# lab2_kondratchenko_buck_boost.net
KiCad netlist of a schematic drawn in Altium Designer
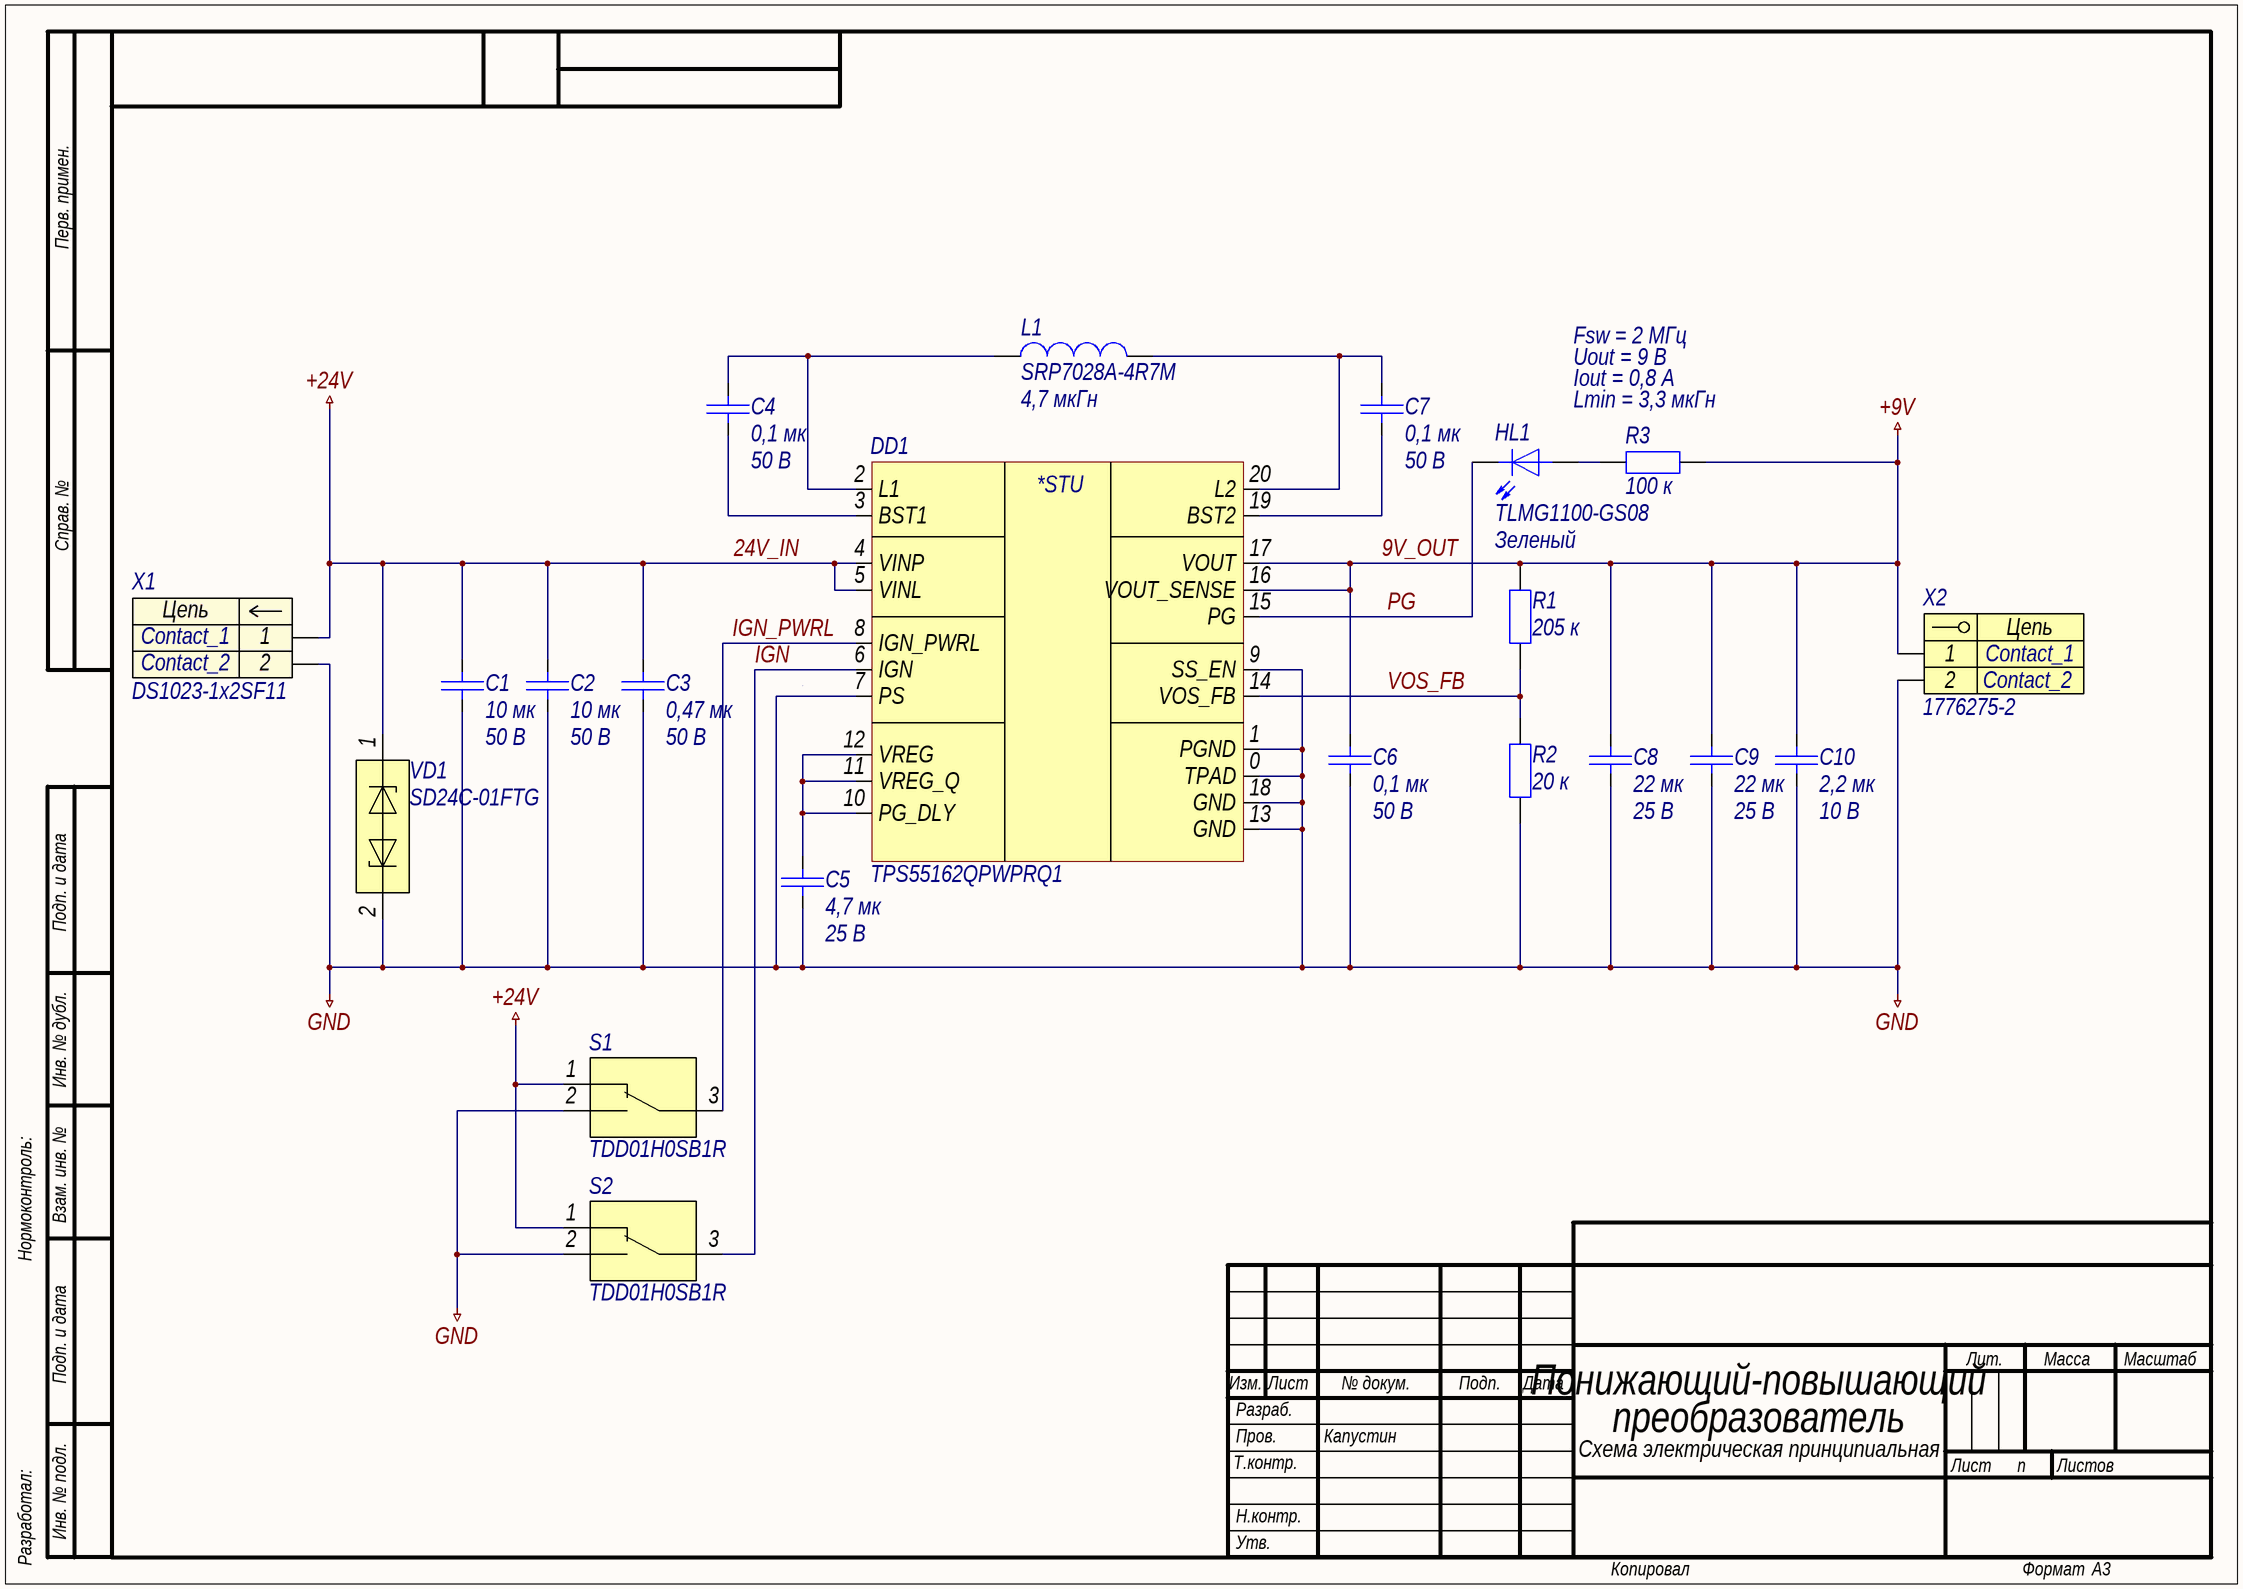
[diagram p0: lab2_kondratchenko_buck_boost.SchDoc]

(export (version "E")
  (design (tool "Eeschema 10.0.6"))
  (components
    (comp (ref "C1")
      (value "10 мк")
      (footprint "C1210")
      (description "=Описание")
      (fields (field (name "НАПРЯЖЕНИЕ") "50 В"))
      (libsource (lib "Database_Students") (part "CAPACITOR-NONPOLAR"))
    )
    (comp (ref "C2")
      (value "10 мк")
      (footprint "C1210")
      (description "=Описание")
      (fields (field (name "НАПРЯЖЕНИЕ") "50 В"))
      (libsource (lib "Database_Students") (part "CAPACITOR-NONPOLAR"))
    )
    (comp (ref "C3")
      (value "0,47 мк")
      (footprint "C0603")
      (description "=Описание")
      (fields (field (name "НАПРЯЖЕНИЕ") "50 В"))
      (libsource (lib "Database_Students") (part "CAPACITOR-NONPOLAR"))
    )
    (comp (ref "C4")
      (value "0,1 мк")
      (footprint "C0603")
      (description "=Описание")
      (fields (field (name "НАПРЯЖЕНИЕ") "50 В"))
      (libsource (lib "Database_Students") (part "CAPACITOR-NONPOLAR"))
    )
    (comp (ref "C5")
      (value "4,7 мк")
      (footprint "C0603")
      (description "=Описание")
      (fields (field (name "НАПРЯЖЕНИЕ") "25 В"))
      (libsource (lib "Database_Students") (part "CAPACITOR-NONPOLAR"))
    )
    (comp (ref "C6")
      (value "0,1 мк")
      (footprint "C0603")
      (description "=Описание")
      (fields (field (name "НАПРЯЖЕНИЕ") "50 В"))
      (libsource (lib "Database_Students") (part "CAPACITOR-NONPOLAR"))
    )
    (comp (ref "C7")
      (value "0,1 мк")
      (footprint "C0603")
      (description "=Описание")
      (fields (field (name "НАПРЯЖЕНИЕ") "50 В"))
      (libsource (lib "Database_Students") (part "CAPACITOR-NONPOLAR"))
    )
    (comp (ref "C8")
      (value "22 мк")
      (footprint "C1210")
      (description "=Описание")
      (fields (field (name "НАПРЯЖЕНИЕ") "25 В"))
      (libsource (lib "Database_Students") (part "CAPACITOR-NONPOLAR"))
    )
    (comp (ref "C9")
      (value "22 мк")
      (footprint "C1210")
      (description "=Описание")
      (fields (field (name "НАПРЯЖЕНИЕ") "25 В"))
      (libsource (lib "Database_Students") (part "CAPACITOR-NONPOLAR"))
    )
    (comp (ref "C10")
      (value "2,2 мк")
      (footprint "C0603")
      (description "=Описание")
      (fields (field (name "НАПРЯЖЕНИЕ") "10 В"))
      (libsource (lib "Database_Students") (part "CAPACITOR-NONPOLAR"))
    )
    (comp (ref "DD1")
      (value "TPS55162QPWPRQ1")
      (footprint "HTSSOP-20-P65-650X440X120-L63X25-T343X275")
      (description "=Описание")
      (libsource (lib "Database_Students") (part "TPS55162QPWPRQ1"))
    )
    (comp (ref "HL1")
      (value "TLMG1100-GS08")
      (footprint "HL0603")
      (description "=Описание")
      (fields (field (name "ЦВЕТ") "Зеленый"))
      (libsource (lib "Database_Students") (part "LED-COMMON"))
    )
    (comp (ref "L1")
      (value "SRP7028A-4R7M")
      (footprint "SRP-2-730X660X280")
      (description "=Описание")
      (fields (field (name "ИНДУКТИВНОСТЬ") "4,7 мкГн"))
      (libsource (lib "Database_Students") (part "INDUCTOR-COMMON"))
    )
    (comp (ref "R1")
      (value "205 к")
      (footprint "R0603")
      (description "=Описание")
      (libsource (lib "Database_Students") (part "RESISTOR-COMMON"))
    )
    (comp (ref "R2")
      (value "20 к")
      (footprint "R0603")
      (description "=Описание")
      (libsource (lib "Database_Students") (part "RESISTOR-COMMON"))
    )
    (comp (ref "R3")
      (value "100 к")
      (footprint "R0603")
      (description "=Описание")
      (libsource (lib "Database_Students") (part "RESISTOR-COMMON"))
    )
    (comp (ref "S1")
      (value "TDD01H0SB1R")
      (footprint "TDD01H0SB1R")
      (description "=Описание")
      (libsource (lib "Database_Students") (part "SWITCH-3C"))
    )
    (comp (ref "S2")
      (value "TDD01H0SB1R")
      (footprint "TDD01H0SB1R")
      (description "=Описание")
      (libsource (lib "Database_Students") (part "SWITCH-3C"))
    )
    (comp (ref "VD1")
      (value "SD24C-01FTG")
      (footprint "SOD-323-257X130X114")
      (description "=Описание")
      (libsource (lib "Database_Students") (part "ZENER-BI-DIRECTIONAL"))
    )
    (comp (ref "X1")
      (value "DS1023-1x2SF11")
      (footprint "DS1069-2MRW6XB")
      (description "=Описание")
      (libsource (lib "Database_Students") (part "HEADER-2-PLG"))
    )
    (comp (ref "X2")
      (value "1776275-2")
      (footprint "1776275-2")
      (description "=Описание")
      (libsource (lib "Database_Students") (part "HEADER-2-TRM"))
    )
  )
  (nets
    (net (code "1") (name "+9V") (class "Default")
      (node (ref "C10") (pin "2") (pinfunction "2_2") (pintype "passive"))
      (node (ref "C6") (pin "2") (pinfunction "2_2") (pintype "passive"))
      (node (ref "C8") (pin "2") (pinfunction "2_2") (pintype "passive"))
      (node (ref "C9") (pin "2") (pinfunction "2_2") (pintype "passive"))
      (node (ref "DD1") (pin "16") (pinfunction "VOUT_SENSE_16") (pintype "passive"))
      (node (ref "DD1") (pin "17") (pinfunction "VOUT_17") (pintype "passive"))
      (node (ref "R1") (pin "1") (pinfunction "1_1") (pintype "passive"))
      (node (ref "R3") (pin "2") (pinfunction "2_2") (pintype "passive"))
      (node (ref "X2") (pin "1") (pinfunction "1_1") (pintype "passive"))
    )
    (net (code "2") (name "+24V") (class "Default")
      (node (ref "C1") (pin "2") (pinfunction "2_2") (pintype "passive"))
      (node (ref "C2") (pin "2") (pinfunction "2_2") (pintype "passive"))
      (node (ref "C3") (pin "2") (pinfunction "2_2") (pintype "passive"))
      (node (ref "DD1") (pin "4") (pinfunction "VINP_4") (pintype "passive"))
      (node (ref "DD1") (pin "5") (pinfunction "VINL_5") (pintype "passive"))
      (node (ref "S1") (pin "1") (pinfunction "1_1") (pintype "passive"))
      (node (ref "S2") (pin "1") (pinfunction "1_1") (pintype "passive"))
      (node (ref "VD1") (pin "1") (pinfunction "1_1") (pintype "passive"))
      (node (ref "X1") (pin "1") (pinfunction "1_1") (pintype "passive"))
    )
    (net (code "3") (name "/IGN") (class "Default")
      (node (ref "DD1") (pin "6") (pinfunction "IGN_6") (pintype "passive"))
      (node (ref "S2") (pin "3") (pinfunction "3_3") (pintype "passive"))
    )
    (net (code "4") (name "/IGN_PWRL") (class "Default")
      (node (ref "DD1") (pin "8") (pinfunction "IGN_PWRL_8") (pintype "passive"))
      (node (ref "S1") (pin "3") (pinfunction "3_3") (pintype "passive"))
    )
    (net (code "5") (name "/PG") (class "Default")
      (node (ref "DD1") (pin "15") (pinfunction "PG_15") (pintype "passive"))
      (node (ref "HL1") (pin "1") (pinfunction "1_1") (pintype "passive"))
    )
    (net (code "6") (name "/VOS_FB") (class "Default")
      (node (ref "DD1") (pin "14") (pinfunction "VOS_FB_14") (pintype "passive"))
      (node (ref "R1") (pin "2") (pinfunction "2_2") (pintype "passive"))
      (node (ref "R2") (pin "2") (pinfunction "2_2") (pintype "passive"))
    )
    (net (code "7") (name "GND") (class "Default")
      (node (ref "C1") (pin "1") (pinfunction "1_1") (pintype "passive"))
      (node (ref "C10") (pin "1") (pinfunction "1_1") (pintype "passive"))
      (node (ref "C2") (pin "1") (pinfunction "1_1") (pintype "passive"))
      (node (ref "C3") (pin "1") (pinfunction "1_1") (pintype "passive"))
      (node (ref "C5") (pin "2") (pinfunction "2_2") (pintype "passive"))
      (node (ref "C6") (pin "1") (pinfunction "1_1") (pintype "passive"))
      (node (ref "C8") (pin "1") (pinfunction "1_1") (pintype "passive"))
      (node (ref "C9") (pin "1") (pinfunction "1_1") (pintype "passive"))
      (node (ref "DD1") (pin "0") (pinfunction "TPAD_0") (pintype "passive"))
      (node (ref "DD1") (pin "1") (pinfunction "PGND_1") (pintype "passive"))
      (node (ref "DD1") (pin "13") (pinfunction "GND_13") (pintype "passive"))
      (node (ref "DD1") (pin "18") (pinfunction "GND_18") (pintype "passive"))
      (node (ref "DD1") (pin "7") (pinfunction "PS_7") (pintype "passive"))
      (node (ref "DD1") (pin "9") (pinfunction "SS_EN_9") (pintype "passive"))
      (node (ref "R2") (pin "1") (pinfunction "1_1") (pintype "passive"))
      (node (ref "S1") (pin "2") (pinfunction "2_2") (pintype "passive"))
      (node (ref "S2") (pin "2") (pinfunction "2_2") (pintype "passive"))
      (node (ref "VD1") (pin "2") (pinfunction "2_2") (pintype "passive"))
      (node (ref "X1") (pin "2") (pinfunction "2_2") (pintype "passive"))
      (node (ref "X2") (pin "2") (pinfunction "2_2") (pintype "passive"))
    )
    (net (code "8") (name "Net-(DD1-BST1)") (class "Default")
      (node (ref "C4") (pin "1") (pinfunction "1_1") (pintype "passive"))
      (node (ref "DD1") (pin "3") (pinfunction "BST1_3") (pintype "passive"))
    )
    (net (code "9") (name "Net-(DD1-BST2)") (class "Default")
      (node (ref "C7") (pin "1") (pinfunction "1_1") (pintype "passive"))
      (node (ref "DD1") (pin "19") (pinfunction "BST2_19") (pintype "passive"))
    )
    (net (code "10") (name "Net-(DD1-L1)") (class "Default")
      (node (ref "C4") (pin "2") (pinfunction "2_2") (pintype "passive"))
      (node (ref "DD1") (pin "2") (pinfunction "L1_2") (pintype "passive"))
      (node (ref "L1") (pin "1") (pinfunction "1_1") (pintype "passive"))
    )
    (net (code "11") (name "Net-(DD1-L2)") (class "Default")
      (node (ref "C7") (pin "2") (pinfunction "2_2") (pintype "passive"))
      (node (ref "DD1") (pin "20") (pinfunction "L2_20") (pintype "passive"))
      (node (ref "L1") (pin "2") (pinfunction "2_2") (pintype "passive"))
    )
    (net (code "12") (name "Net-(DD1-PG_DLY)") (class "Default")
      (node (ref "C5") (pin "1") (pinfunction "1_1") (pintype "passive"))
      (node (ref "DD1") (pin "10") (pinfunction "PG_DLY_10") (pintype "passive"))
      (node (ref "DD1") (pin "11") (pinfunction "VREG_Q_11") (pintype "passive"))
      (node (ref "DD1") (pin "12") (pinfunction "VREG_12") (pintype "passive"))
    )
    (net (code "13") (name "Net-(HL1-Pad2)") (class "Default")
      (node (ref "HL1") (pin "2") (pinfunction "2_2") (pintype "passive"))
      (node (ref "R3") (pin "1") (pinfunction "1_1") (pintype "passive"))
    )
  )
)
